# eeZee_microSD.net
KiCad netlist of a schematic drawn in EAGLE
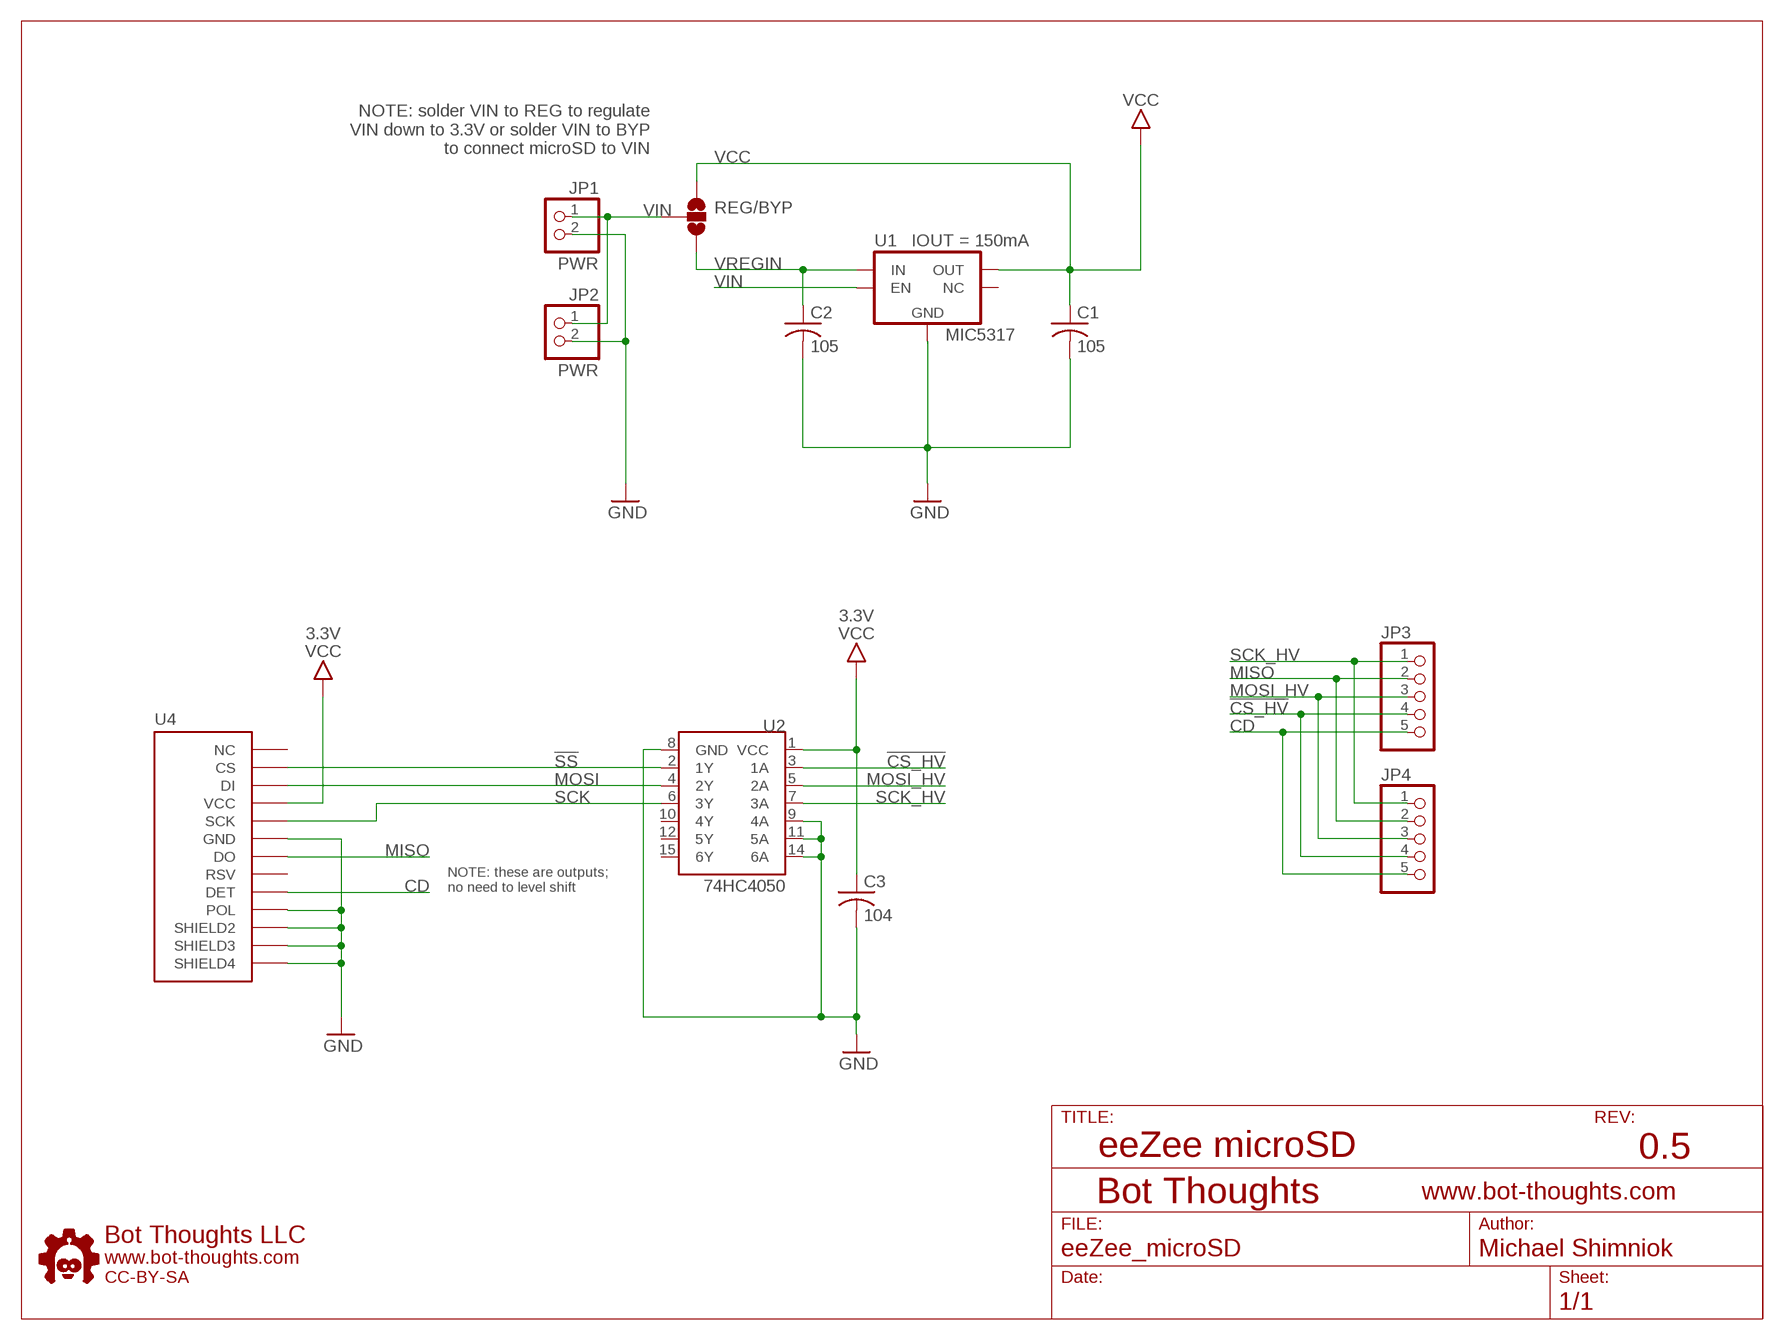
[diagram p0: schematic, sheet 1]

(export (version "E")
  (design (tool "Eeschema 10.0.6"))
  (components
    (comp (ref "C1")
      (value "105")
      (footprint "eagle-import:0603")
      (fields (field (name "PARTNO") "LMK107B7105KA-T"))
      (libsource (lib "eagle-import") (part "C-0603"))
    )
    (comp (ref "C2")
      (value "105")
      (footprint "eagle-import:0603")
      (fields (field (name "PARTNO") "LMK107B7105KA-T"))
      (libsource (lib "eagle-import") (part "C-0603"))
    )
    (comp (ref "C3")
      (value "104")
      (footprint "eagle-import:C0603")
      (fields (field (name "PARTNO") "LMK107B7105KA-T"))
      (libsource (lib "eagle-import") (part "C-USC0603"))
    )
    (comp (ref "JP1")
      (value "PWR")
      (footprint "eagle-import:1X02-S")
      (libsource (lib "eagle-import") (part "PINHD-1X02_2.54-S"))
    )
    (comp (ref "JP2")
      (value "PWR")
      (footprint "eagle-import:1X02-S")
      (libsource (lib "eagle-import") (part "PINHD-1X02_2.54-S"))
    )
    (comp (ref "JP3")
      (value "PINHD-1X05_2.54-S")
      (footprint "eagle-import:1X05-S")
      (libsource (lib "eagle-import") (part "PINHD-1X05_2.54-S"))
    )
    (comp (ref "JP4")
      (value "PINHD-1X05_2.54-S")
      (footprint "eagle-import:1X05-S")
      (libsource (lib "eagle-import") (part "PINHD-1X05_2.54-S"))
    )
    (comp (ref "REG/BYP")
      (value "SOLDERJUMPER_2WAYS")
      (footprint "eagle-import:SJ_3")
      (libsource (lib "eagle-import") (part "SOLDERJUMPER_2WAYS"))
    )
    (comp (ref "U$5")
      (value "BTLOGO-LOGO-SM")
      (footprint "eagle-import:BTLOGOS")
      (libsource (lib "eagle-import") (part "BTLOGO-LOGO-SM"))
    )
    (comp (ref "U1")
      (value "MIC5317")
      (footprint "eagle-import:SOT23-5")
      (fields
        (field (name "IOUT") "150mA")
        (field (name "PARTNO") "MIC5317-3.3YM5-TR")
        (field (name "VOUT") "3.3V")
      )
      (libsource (lib "eagle-import") (part "MIC5317"))
    )
    (comp (ref "U2")
      (value "74HC4050")
      (footprint "eagle-import:SO016")
      (libsource (lib "eagle-import") (part "HEX_CONVERTER"))
    )
    (comp (ref "U4")
      (value "MICROSD_CD")
      (footprint "eagle-import:USD_SMALL")
      (libsource (lib "eagle-import") (part "MICROSD_CD"))
    )
  )
  (nets
    (net (code "1") (name "/CD") (class "Default")
      (node (ref "JP3") (pin "5") (pinfunction "5_5") (pintype "passive"))
      (node (ref "JP4") (pin "5") (pinfunction "5_5") (pintype "passive"))
      (node (ref "U4") (pin "DET") (pinfunction "DET_DET") (pintype "bidirectional"))
    )
    (net (code "2") (name "/MISO") (class "Default")
      (node (ref "JP3") (pin "2") (pinfunction "2_2") (pintype "passive"))
      (node (ref "JP4") (pin "2") (pinfunction "2_2") (pintype "passive"))
      (node (ref "U4") (pin "7") (pinfunction "DO_7") (pintype "bidirectional"))
    )
    (net (code "3") (name "/MOSI") (class "Default")
      (node (ref "U2") (pin "4") (pinfunction "2Y_4") (pintype "bidirectional"))
      (node (ref "U4") (pin "3") (pinfunction "DI_3") (pintype "bidirectional"))
    )
    (net (code "4") (name "/MOSI_HV") (class "Default")
      (node (ref "JP3") (pin "3") (pinfunction "3_3") (pintype "passive"))
      (node (ref "JP4") (pin "3") (pinfunction "3_3") (pintype "passive"))
      (node (ref "U2") (pin "5") (pinfunction "2A_5") (pintype "bidirectional"))
    )
    (net (code "5") (name "/SCK") (class "Default")
      (node (ref "U2") (pin "6") (pinfunction "3Y_6") (pintype "bidirectional"))
      (node (ref "U4") (pin "5") (pinfunction "SCK_5") (pintype "bidirectional"))
    )
    (net (code "6") (name "/SCK_HV") (class "Default")
      (node (ref "JP3") (pin "1") (pinfunction "1_1") (pintype "passive"))
      (node (ref "JP4") (pin "1") (pinfunction "1_1") (pintype "passive"))
      (node (ref "U2") (pin "7") (pinfunction "3A_7") (pintype "bidirectional"))
    )
    (net (code "7") (name "/VIN") (class "Default")
      (node (ref "JP1") (pin "1") (pinfunction "1_1") (pintype "passive"))
      (node (ref "JP2") (pin "1") (pinfunction "1_1") (pintype "passive"))
      (node (ref "REG/BYP") (pin "2") (pinfunction "2_2") (pintype "passive"))
      (node (ref "U1") (pin "3") (pinfunction "EN_3") (pintype "input"))
    )
    (net (code "8") (name "/VREGIN") (class "Default")
      (node (ref "C2") (pin "1") (pinfunction "+_1") (pintype "passive"))
      (node (ref "REG/BYP") (pin "3") (pinfunction "3_3") (pintype "passive"))
      (node (ref "U1") (pin "1") (pinfunction "IN_1") (pintype "power_in"))
    )
    (net (code "9") (name "/~{CS_HV}") (class "Default")
      (node (ref "JP3") (pin "4") (pinfunction "4_4") (pintype "passive"))
      (node (ref "JP4") (pin "4") (pinfunction "4_4") (pintype "passive"))
      (node (ref "U2") (pin "3") (pinfunction "1A_3") (pintype "bidirectional"))
    )
    (net (code "10") (name "/~{SS}") (class "Default")
      (node (ref "U2") (pin "2") (pinfunction "1Y_2") (pintype "bidirectional"))
      (node (ref "U4") (pin "2") (pinfunction "CS_2") (pintype "bidirectional"))
    )
    (net (code "11") (name "3.3V") (class "Default")
      (node (ref "C1") (pin "1") (pinfunction "+_1") (pintype "passive"))
      (node (ref "C3") (pin "1") (pinfunction "1_1") (pintype "passive"))
      (node (ref "REG/BYP") (pin "1") (pinfunction "1_1") (pintype "passive"))
      (node (ref "U1") (pin "5") (pinfunction "OUT_5") (pintype "power_in"))
      (node (ref "U2") (pin "1") (pinfunction "VCC_1") (pintype "bidirectional"))
      (node (ref "U4") (pin "4") (pinfunction "VCC_4") (pintype "bidirectional"))
    )
    (net (code "12") (name "GND") (class "Default")
      (node (ref "C1") (pin "2") (pinfunction "-_2") (pintype "passive"))
      (node (ref "C2") (pin "2") (pinfunction "-_2") (pintype "passive"))
      (node (ref "C3") (pin "2") (pinfunction "2_2") (pintype "passive"))
      (node (ref "JP1") (pin "2") (pinfunction "2_2") (pintype "passive"))
      (node (ref "JP2") (pin "2") (pinfunction "2_2") (pintype "passive"))
      (node (ref "U1") (pin "2") (pinfunction "GND_2") (pintype "power_in"))
      (node (ref "U2") (pin "11") (pinfunction "5A_11") (pintype "bidirectional"))
      (node (ref "U2") (pin "14") (pinfunction "6A_14") (pintype "bidirectional"))
      (node (ref "U2") (pin "8") (pinfunction "GND_8") (pintype "bidirectional"))
      (node (ref "U2") (pin "9") (pinfunction "4A_9") (pintype "bidirectional"))
      (node (ref "U4") (pin "6") (pinfunction "GND_6") (pintype "bidirectional"))
      (node (ref "U4") (pin "GND1") (pinfunction "SHIELD2_GND1") (pintype "bidirectional"))
      (node (ref "U4") (pin "GND3") (pinfunction "SHIELD3_GND3") (pintype "bidirectional"))
      (node (ref "U4") (pin "GND4") (pinfunction "SHIELD4_GND4") (pintype "bidirectional"))
      (node (ref "U4") (pin "POL") (pinfunction "POL_POL") (pintype "bidirectional"))
    )
    (net (code "13") (name "unconnected-(U1-NC-Pad4)") (class "Default")
      (node (ref "U1") (pin "4") (pinfunction "NC_4") (pintype "no_connect"))
    )
    (net (code "14") (name "unconnected-(U2-4Y-Pad10)") (class "Default")
      (node (ref "U2") (pin "10") (pinfunction "4Y_10") (pintype "bidirectional"))
    )
    (net (code "15") (name "unconnected-(U2-5Y-Pad12)") (class "Default")
      (node (ref "U2") (pin "12") (pinfunction "5Y_12") (pintype "bidirectional"))
    )
    (net (code "16") (name "unconnected-(U2-6Y-Pad15)") (class "Default")
      (node (ref "U2") (pin "15") (pinfunction "6Y_15") (pintype "bidirectional"))
    )
    (net (code "17") (name "unconnected-(U4-NC-Pad1)") (class "Default")
      (node (ref "U4") (pin "1") (pinfunction "NC_1") (pintype "bidirectional"))
    )
    (net (code "18") (name "unconnected-(U4-RSV-Pad8)") (class "Default")
      (node (ref "U4") (pin "8") (pinfunction "RSV_8") (pintype "bidirectional"))
    )
  )
)
